# 1V8BUCK.net
KiCad netlist of a schematic drawn in Altium Designer
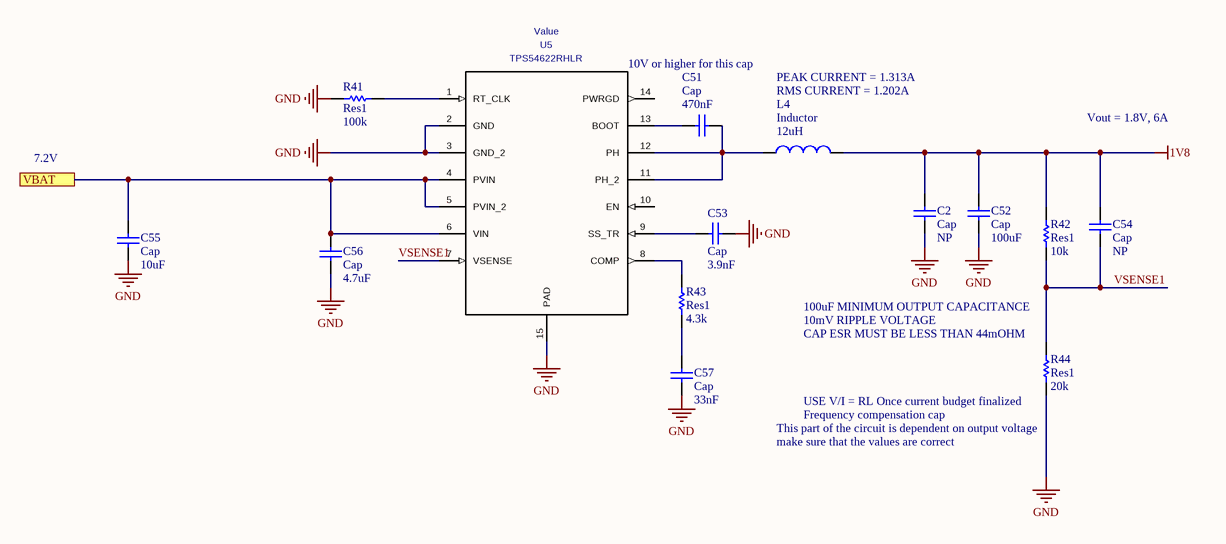
[diagram p0: 1V8BUCK.SchDoc]

(export (version "E")
  (design (tool "Eeschema 10.0.6"))
  (components
    (comp (ref "C2")
      (value "Cap")
      (footprint "1608[0603]")
      (description "Capacitor")
      (fields (field (name "ALTIUM_VALUE") "NP") (field (name "PUBLISHER") "Altium Limited"))
      (libsource (lib "Miscellaneous Devices") (part "Cap"))
    )
    (comp (ref "C51")
      (value "Cap")
      (footprint "0402-A")
      (description "Capacitor")
      (fields (field (name "ALTIUM_VALUE") "470nF") (field (name "PUBLISHER") "Altium Limited"))
      (libsource (lib "Miscellaneous Devices") (part "Cap"))
    )
    (comp (ref "C52")
      (value "Cap")
      (footprint "C1210")
      (description "Capacitor")
      (fields (field (name "ALTIUM_VALUE") "100uF") (field (name "PUBLISHER") "Altium Limited"))
      (libsource (lib "Miscellaneous Devices") (part "Cap"))
    )
    (comp (ref "C53")
      (value "Cap")
      (footprint "0402-A")
      (description "Capacitor")
      (fields (field (name "ALTIUM_VALUE") "3.9nF") (field (name "PUBLISHER") "Altium Limited"))
      (libsource (lib "Miscellaneous Devices") (part "Cap"))
    )
    (comp (ref "C54")
      (value "Cap")
      (footprint "1608[0603]")
      (description "Capacitor")
      (fields (field (name "ALTIUM_VALUE") "NP") (field (name "PUBLISHER") "Altium Limited"))
      (libsource (lib "Miscellaneous Devices") (part "Cap"))
    )
    (comp (ref "C55")
      (value "Cap")
      (footprint "6-0805_M")
      (description "Capacitor")
      (fields (field (name "ALTIUM_VALUE") "10uF") (field (name "PUBLISHER") "Altium Limited"))
      (libsource (lib "Miscellaneous Devices") (part "Cap"))
    )
    (comp (ref "C56")
      (value "Cap")
      (footprint "6-0805_M")
      (description "Capacitor")
      (fields (field (name "ALTIUM_VALUE") "4.7uF") (field (name "PUBLISHER") "Altium Limited"))
      (libsource (lib "Miscellaneous Devices") (part "Cap"))
    )
    (comp (ref "C57")
      (value "Cap")
      (footprint "0402-A")
      (description "Capacitor")
      (fields (field (name "ALTIUM_VALUE") "33nF") (field (name "PUBLISHER") "Altium Limited"))
      (libsource (lib "Miscellaneous Devices") (part "Cap"))
    )
    (comp (ref "L4")
      (value "Inductor")
      (footprint "IND_BOURNS_SRR1260")
      (fields (field (name "ALTIUM_VALUE") "12uH") (field (name "PUBLISHER") "Altium Limited"))
      (libsource (lib "Miscellaneous Devices") (part "Inductor"))
    )
    (comp (ref "R41")
      (value "Res1")
      (footprint "0402-A")
      (description "Resistor")
      (fields (field (name "ALTIUM_VALUE") "100k") (field (name "PUBLISHER") "Altium Limited"))
      (libsource (lib "Miscellaneous Devices") (part "Res1"))
    )
    (comp (ref "R42")
      (value "Res1")
      (footprint "0402-A")
      (description "Resistor")
      (fields (field (name "ALTIUM_VALUE") "10k") (field (name "PUBLISHER") "Altium Limited"))
      (libsource (lib "Miscellaneous Devices") (part "Res1"))
    )
    (comp (ref "R43")
      (value "Res1")
      (footprint "0402-A")
      (description "Resistor")
      (fields (field (name "ALTIUM_VALUE") "4.3k") (field (name "PUBLISHER") "Altium Limited"))
      (libsource (lib "Miscellaneous Devices") (part "Res1"))
    )
    (comp (ref "R44")
      (value "Res1")
      (footprint "0402-A")
      (description "Resistor")
      (fields (field (name "ALTIUM_VALUE") "20k") (field (name "PUBLISHER") "Altium Limited"))
      (libsource (lib "Miscellaneous Devices") (part "Res1"))
    )
    (comp (ref "U5")
      (value "TPS54622RHLR")
      (footprint "RHL0014A")
      (fields (field (name "MANUFACTURER") "Texas Instruments") (field (name "ALTIUM_VALUE") "Value"))
      (libsource (lib "AltiumV15") (part "TPS54622RHLR"))
    )
  )
  (nets
    (net (code "1") (name "/VBAT") (class "Default")
      (node (ref "C55") (pin "2") (pinfunction "2_2") (pintype "passive"))
      (node (ref "C56") (pin "2") (pinfunction "2_2") (pintype "passive"))
      (node (ref "U5") (pin "4") (pinfunction "PVIN_4") (pintype "power_in"))
      (node (ref "U5") (pin "5") (pinfunction "PVIN_2_5") (pintype "power_in"))
      (node (ref "U5") (pin "6") (pinfunction "VIN_6") (pintype "power_in"))
    )
    (net (code "2") (name "/VSENSE1") (class "Default")
      (node (ref "C54") (pin "1") (pinfunction "1_1") (pintype "passive"))
      (node (ref "R42") (pin "2") (pinfunction "2_2") (pintype "passive"))
      (node (ref "R44") (pin "2") (pinfunction "2_2") (pintype "passive"))
      (node (ref "U5") (pin "7") (pinfunction "VSENSE_7") (pintype "input"))
    )
    (net (code "3") (name "1V8") (class "Default")
      (node (ref "C2") (pin "2") (pinfunction "2_2") (pintype "passive"))
      (node (ref "C52") (pin "2") (pinfunction "2_2") (pintype "passive"))
      (node (ref "C54") (pin "2") (pinfunction "2_2") (pintype "passive"))
      (node (ref "L4") (pin "2") (pinfunction "2_2") (pintype "passive"))
      (node (ref "R42") (pin "1") (pinfunction "1_1") (pintype "passive"))
    )
    (net (code "4") (name "GND") (class "Default")
      (node (ref "C2") (pin "1") (pinfunction "1_1") (pintype "passive"))
      (node (ref "C52") (pin "1") (pinfunction "1_1") (pintype "passive"))
      (node (ref "C53") (pin "1") (pinfunction "1_1") (pintype "passive"))
      (node (ref "C55") (pin "1") (pinfunction "1_1") (pintype "passive"))
      (node (ref "C56") (pin "1") (pinfunction "1_1") (pintype "passive"))
      (node (ref "C57") (pin "1") (pinfunction "1_1") (pintype "passive"))
      (node (ref "R41") (pin "1") (pinfunction "1_1") (pintype "passive"))
      (node (ref "R44") (pin "1") (pinfunction "1_1") (pintype "passive"))
      (node (ref "U5") (pin "15") (pinfunction "PAD_15") (pintype "power_in"))
      (node (ref "U5") (pin "2") (pinfunction "GND_2") (pintype "power_in"))
      (node (ref "U5") (pin "3") (pinfunction "GND_2_3") (pintype "power_in"))
    )
    (net (code "5") (name "Net-(C57-Pad2)") (class "Default")
      (node (ref "C57") (pin "2") (pinfunction "2_2") (pintype "passive"))
      (node (ref "R43") (pin "1") (pinfunction "1_1") (pintype "passive"))
    )
    (net (code "6") (name "Net-(U5-BOOT)") (class "Default")
      (node (ref "C51") (pin "1") (pinfunction "1_1") (pintype "passive"))
      (node (ref "U5") (pin "13") (pinfunction "BOOT_13") (pintype "power_in"))
    )
    (net (code "7") (name "Net-(U5-COMP)") (class "Default")
      (node (ref "R43") (pin "2") (pinfunction "2_2") (pintype "passive"))
      (node (ref "U5") (pin "8") (pinfunction "COMP_8") (pintype "output"))
    )
    (net (code "8") (name "Net-(U5-PH)") (class "Default")
      (node (ref "C51") (pin "2") (pinfunction "2_2") (pintype "passive"))
      (node (ref "L4") (pin "1") (pinfunction "1_1") (pintype "passive"))
      (node (ref "U5") (pin "11") (pinfunction "PH_2_11") (pintype "power_in"))
      (node (ref "U5") (pin "12") (pinfunction "PH_12") (pintype "power_in"))
    )
    (net (code "9") (name "Net-(U5-RT_CLK)") (class "Default")
      (node (ref "R41") (pin "2") (pinfunction "2_2") (pintype "passive"))
      (node (ref "U5") (pin "1") (pinfunction "RT_CLK_1") (pintype "input"))
    )
    (net (code "10") (name "Net-(U5-SS_TR)") (class "Default")
      (node (ref "C53") (pin "2") (pinfunction "2_2") (pintype "passive"))
      (node (ref "U5") (pin "9") (pinfunction "SS_TR_9") (pintype "input"))
    )
    (net (code "11") (name "unconnected-(U5-EN-Pad10)") (class "Default")
      (node (ref "U5") (pin "10") (pinfunction "EN_10") (pintype "input"))
    )
    (net (code "12") (name "unconnected-(U5-PWRGD-Pad14)") (class "Default")
      (node (ref "U5") (pin "14") (pinfunction "PWRGD_14") (pintype "output"))
    )
  )
)
